# Memory.net
KiCad netlist of a schematic drawn in Altium Designer
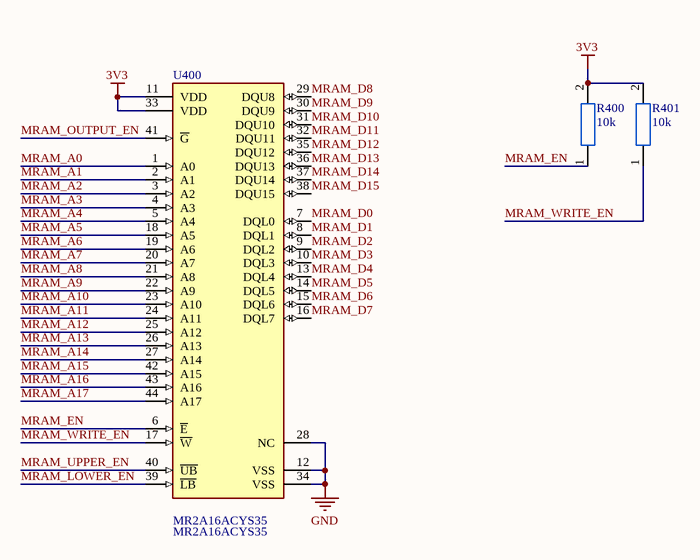
[diagram p0: Memory.SchDoc]

(export (version "E")
  (design (tool "Eeschema 10.0.6"))
  (components
    (comp (ref "R400")
      (value "10k")
      (footprint "0402_footprint")
      (libsource (lib "Schlib1") (part "Resistor_0402"))
    )
    (comp (ref "R401")
      (value "10k")
      (footprint "0402_footprint")
      (libsource (lib "Schlib1") (part "Resistor_0402"))
    )
    (comp (ref "U400")
      (value "MR2A16ACYS35")
      (footprint "Everspin_MR2A16ACYS35_0")
      (description "IC RAM 4M PARALLEL 44TSOP2")
      (fields
        (field (name "DIGIKEY PART NUMBER") "819-1011-ND")
        (field (name "MOUSER PART NUMBER") "936-MR2A16ACYS35")
      )
      (libsource (lib "Kaunas University of Technology") (part "MR2A16ACYS35"))
    )
  )
  (nets
    (net (code "1") (name "/MRAM_A0") (class "Default")
      (node (ref "U400") (pin "1") (pinfunction "A0_1") (pintype "input"))
    )
    (net (code "2") (name "/MRAM_A1") (class "Default")
      (node (ref "U400") (pin "2") (pinfunction "A1_2") (pintype "input"))
    )
    (net (code "3") (name "/MRAM_A2") (class "Default")
      (node (ref "U400") (pin "3") (pinfunction "A2_3") (pintype "input"))
    )
    (net (code "4") (name "/MRAM_A3") (class "Default")
      (node (ref "U400") (pin "4") (pinfunction "A3_4") (pintype "input"))
    )
    (net (code "5") (name "/MRAM_A4") (class "Default")
      (node (ref "U400") (pin "5") (pinfunction "A4_5") (pintype "input"))
    )
    (net (code "6") (name "/MRAM_A5") (class "Default")
      (node (ref "U400") (pin "18") (pinfunction "A5_18") (pintype "input"))
    )
    (net (code "7") (name "/MRAM_A6") (class "Default")
      (node (ref "U400") (pin "19") (pinfunction "A6_19") (pintype "input"))
    )
    (net (code "8") (name "/MRAM_A7") (class "Default")
      (node (ref "U400") (pin "20") (pinfunction "A7_20") (pintype "input"))
    )
    (net (code "9") (name "/MRAM_A8") (class "Default")
      (node (ref "U400") (pin "21") (pinfunction "A8_21") (pintype "input"))
    )
    (net (code "10") (name "/MRAM_A9") (class "Default")
      (node (ref "U400") (pin "22") (pinfunction "A9_22") (pintype "input"))
    )
    (net (code "11") (name "/MRAM_A10") (class "Default")
      (node (ref "U400") (pin "23") (pinfunction "A10_23") (pintype "input"))
    )
    (net (code "12") (name "/MRAM_A11") (class "Default")
      (node (ref "U400") (pin "24") (pinfunction "A11_24") (pintype "input"))
    )
    (net (code "13") (name "/MRAM_A12") (class "Default")
      (node (ref "U400") (pin "25") (pinfunction "A12_25") (pintype "input"))
    )
    (net (code "14") (name "/MRAM_A13") (class "Default")
      (node (ref "U400") (pin "26") (pinfunction "A13_26") (pintype "input"))
    )
    (net (code "15") (name "/MRAM_A14") (class "Default")
      (node (ref "U400") (pin "27") (pinfunction "A14_27") (pintype "input"))
    )
    (net (code "16") (name "/MRAM_A15") (class "Default")
      (node (ref "U400") (pin "42") (pinfunction "A15_42") (pintype "input"))
    )
    (net (code "17") (name "/MRAM_A16") (class "Default")
      (node (ref "U400") (pin "43") (pinfunction "A16_43") (pintype "input"))
    )
    (net (code "18") (name "/MRAM_A17") (class "Default")
      (node (ref "U400") (pin "44") (pinfunction "A17_44") (pintype "input"))
    )
    (net (code "19") (name "/MRAM_D0") (class "Default")
      (node (ref "U400") (pin "7") (pinfunction "DQL0_7") (pintype "bidirectional"))
    )
    (net (code "20") (name "/MRAM_D1") (class "Default")
      (node (ref "U400") (pin "8") (pinfunction "DQL1_8") (pintype "bidirectional"))
    )
    (net (code "21") (name "/MRAM_D2") (class "Default")
      (node (ref "U400") (pin "9") (pinfunction "DQL2_9") (pintype "bidirectional"))
    )
    (net (code "22") (name "/MRAM_D3") (class "Default")
      (node (ref "U400") (pin "10") (pinfunction "DQL3_10") (pintype "bidirectional"))
    )
    (net (code "23") (name "/MRAM_D4") (class "Default")
      (node (ref "U400") (pin "13") (pinfunction "DQL4_13") (pintype "bidirectional"))
    )
    (net (code "24") (name "/MRAM_D5") (class "Default")
      (node (ref "U400") (pin "14") (pinfunction "DQL5_14") (pintype "bidirectional"))
    )
    (net (code "25") (name "/MRAM_D6") (class "Default")
      (node (ref "U400") (pin "15") (pinfunction "DQL6_15") (pintype "bidirectional"))
    )
    (net (code "26") (name "/MRAM_D7") (class "Default")
      (node (ref "U400") (pin "16") (pinfunction "DQL7_16") (pintype "bidirectional"))
    )
    (net (code "27") (name "/MRAM_D8") (class "Default")
      (node (ref "U400") (pin "29") (pinfunction "DQU8_29") (pintype "bidirectional"))
    )
    (net (code "28") (name "/MRAM_D9") (class "Default")
      (node (ref "U400") (pin "30") (pinfunction "DQU9_30") (pintype "bidirectional"))
    )
    (net (code "29") (name "/MRAM_D10") (class "Default")
      (node (ref "U400") (pin "31") (pinfunction "DQU10_31") (pintype "bidirectional"))
    )
    (net (code "30") (name "/MRAM_D11") (class "Default")
      (node (ref "U400") (pin "32") (pinfunction "DQU11_32") (pintype "bidirectional"))
    )
    (net (code "31") (name "/MRAM_D12") (class "Default")
      (node (ref "U400") (pin "35") (pinfunction "DQU12_35") (pintype "bidirectional"))
    )
    (net (code "32") (name "/MRAM_D13") (class "Default")
      (node (ref "U400") (pin "36") (pinfunction "DQU13_36") (pintype "bidirectional"))
    )
    (net (code "33") (name "/MRAM_D14") (class "Default")
      (node (ref "U400") (pin "37") (pinfunction "DQU14_37") (pintype "bidirectional"))
    )
    (net (code "34") (name "/MRAM_D15") (class "Default")
      (node (ref "U400") (pin "38") (pinfunction "DQU15_38") (pintype "bidirectional"))
    )
    (net (code "35") (name "/MRAM_EN") (class "Default")
      (node (ref "R400") (pin "1") (pinfunction "1_1") (pintype "passive"))
      (node (ref "U400") (pin "6") (pinfunction "~{E}_6") (pintype "input"))
    )
    (net (code "36") (name "/MRAM_LOWER_EN") (class "Default")
      (node (ref "U400") (pin "39") (pinfunction "~{LB}_39") (pintype "input"))
    )
    (net (code "37") (name "/MRAM_OUTPUT_EN") (class "Default")
      (node (ref "U400") (pin "41") (pinfunction "~{G}_41") (pintype "input"))
    )
    (net (code "38") (name "/MRAM_UPPER_EN") (class "Default")
      (node (ref "U400") (pin "40") (pinfunction "~{UB}_40") (pintype "input"))
    )
    (net (code "39") (name "/MRAM_WRITE_EN") (class "Default")
      (node (ref "R401") (pin "1") (pinfunction "1_1") (pintype "passive"))
      (node (ref "U400") (pin "17") (pinfunction "~{W}_17") (pintype "input"))
    )
    (net (code "40") (name "3V3") (class "Default")
      (node (ref "R400") (pin "2") (pinfunction "2_2") (pintype "passive"))
      (node (ref "R401") (pin "2") (pinfunction "2_2") (pintype "passive"))
      (node (ref "U400") (pin "11") (pinfunction "VDD_11") (pintype "power_in"))
      (node (ref "U400") (pin "33") (pinfunction "VDD_33") (pintype "power_in"))
    )
    (net (code "41") (name "GND") (class "Default")
      (node (ref "U400") (pin "12") (pinfunction "VSS_12") (pintype "power_in"))
      (node (ref "U400") (pin "28") (pinfunction "NC_28") (pintype "passive"))
      (node (ref "U400") (pin "34") (pinfunction "VSS_34") (pintype "power_in"))
    )
  )
)
